# TRS.net
KiCad netlist of a schematic drawn in EAGLE
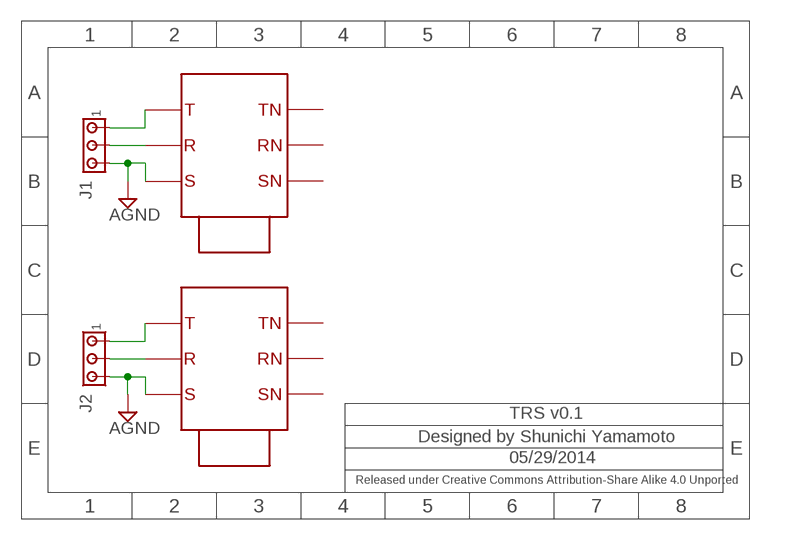
[diagram p0: schematic, sheet 1]

(export (version "E")
  (design (tool "Eeschema 10.0.6"))
  (components
    (comp (ref "J1")
      (value "MTA03-100")
      (footprint "eagle-import:10X03MTA")
      (libsource (lib "eagle-import") (part "MTA03-100"))
    )
    (comp (ref "J2")
      (value "MTA03-100")
      (footprint "eagle-import:10X03MTA")
      (libsource (lib "eagle-import") (part "MTA03-100"))
    )
    (comp (ref "X1")
      (value "NMJ6HFD2")
      (footprint "eagle-import:NMJ6HFD2")
      (libsource (lib "eagle-import") (part "NMJ6HFD2"))
    )
    (comp (ref "X2")
      (value "NMJ6HFD2")
      (footprint "eagle-import:NMJ6HFD2")
      (libsource (lib "eagle-import") (part "NMJ6HFD2"))
    )
  )
  (nets
    (net (code "1") (name "AGND") (class "Default")
      (node (ref "J1") (pin "3") (pinfunction "3_3") (pintype "passive"))
      (node (ref "J2") (pin "3") (pinfunction "3_3") (pintype "passive"))
      (node (ref "X1") (pin "GND-IN") (pinfunction "GND-IN_GND-IN") (pintype "input"))
      (node (ref "X2") (pin "GND-IN") (pinfunction "GND-IN_GND-IN") (pintype "input"))
    )
    (net (code "2") (name "Net-(J1-Pad1)") (class "Default")
      (node (ref "J1") (pin "1") (pinfunction "1_1") (pintype "passive"))
      (node (ref "X1") (pin "LEFT-IN") (pinfunction "LEFT-IN_LEFT-IN") (pintype "input"))
    )
    (net (code "3") (name "Net-(J1-Pad2)") (class "Default")
      (node (ref "J1") (pin "2") (pinfunction "2_2") (pintype "passive"))
      (node (ref "X1") (pin "RIGHT-IN") (pinfunction "RIGHT-IN_RIGHT-IN") (pintype "input"))
    )
    (net (code "4") (name "Net-(J2-Pad1)") (class "Default")
      (node (ref "J2") (pin "1") (pinfunction "1_1") (pintype "passive"))
      (node (ref "X2") (pin "LEFT-IN") (pinfunction "LEFT-IN_LEFT-IN") (pintype "input"))
    )
    (net (code "5") (name "Net-(J2-Pad2)") (class "Default")
      (node (ref "J2") (pin "2") (pinfunction "2_2") (pintype "passive"))
      (node (ref "X2") (pin "RIGHT-IN") (pinfunction "RIGHT-IN_RIGHT-IN") (pintype "input"))
    )
    (net (code "6") (name "unconnected-(X1-PadGND-OUT)") (class "Default")
      (node (ref "X1") (pin "GND-OUT") (pinfunction "GND-OUT_GND-OUT") (pintype "output"))
    )
    (net (code "7") (name "unconnected-(X1-PadLEFT-OUT)") (class "Default")
      (node (ref "X1") (pin "LEFT-OUT") (pinfunction "LEFT-OUT_LEFT-OUT") (pintype "output"))
    )
    (net (code "8") (name "unconnected-(X1-PadRIGHT-OUT)") (class "Default")
      (node (ref "X1") (pin "RIGHT-OUT") (pinfunction "RIGHT-OUT_RIGHT-OUT") (pintype "output"))
    )
    (net (code "9") (name "unconnected-(X2-PadGND-OUT)") (class "Default")
      (node (ref "X2") (pin "GND-OUT") (pinfunction "GND-OUT_GND-OUT") (pintype "output"))
    )
    (net (code "10") (name "unconnected-(X2-PadLEFT-OUT)") (class "Default")
      (node (ref "X2") (pin "LEFT-OUT") (pinfunction "LEFT-OUT_LEFT-OUT") (pintype "output"))
    )
    (net (code "11") (name "unconnected-(X2-PadRIGHT-OUT)") (class "Default")
      (node (ref "X2") (pin "RIGHT-OUT") (pinfunction "RIGHT-OUT_RIGHT-OUT") (pintype "output"))
    )
  )
)
